# power.net
KiCad netlist of a schematic drawn in Altium Designer
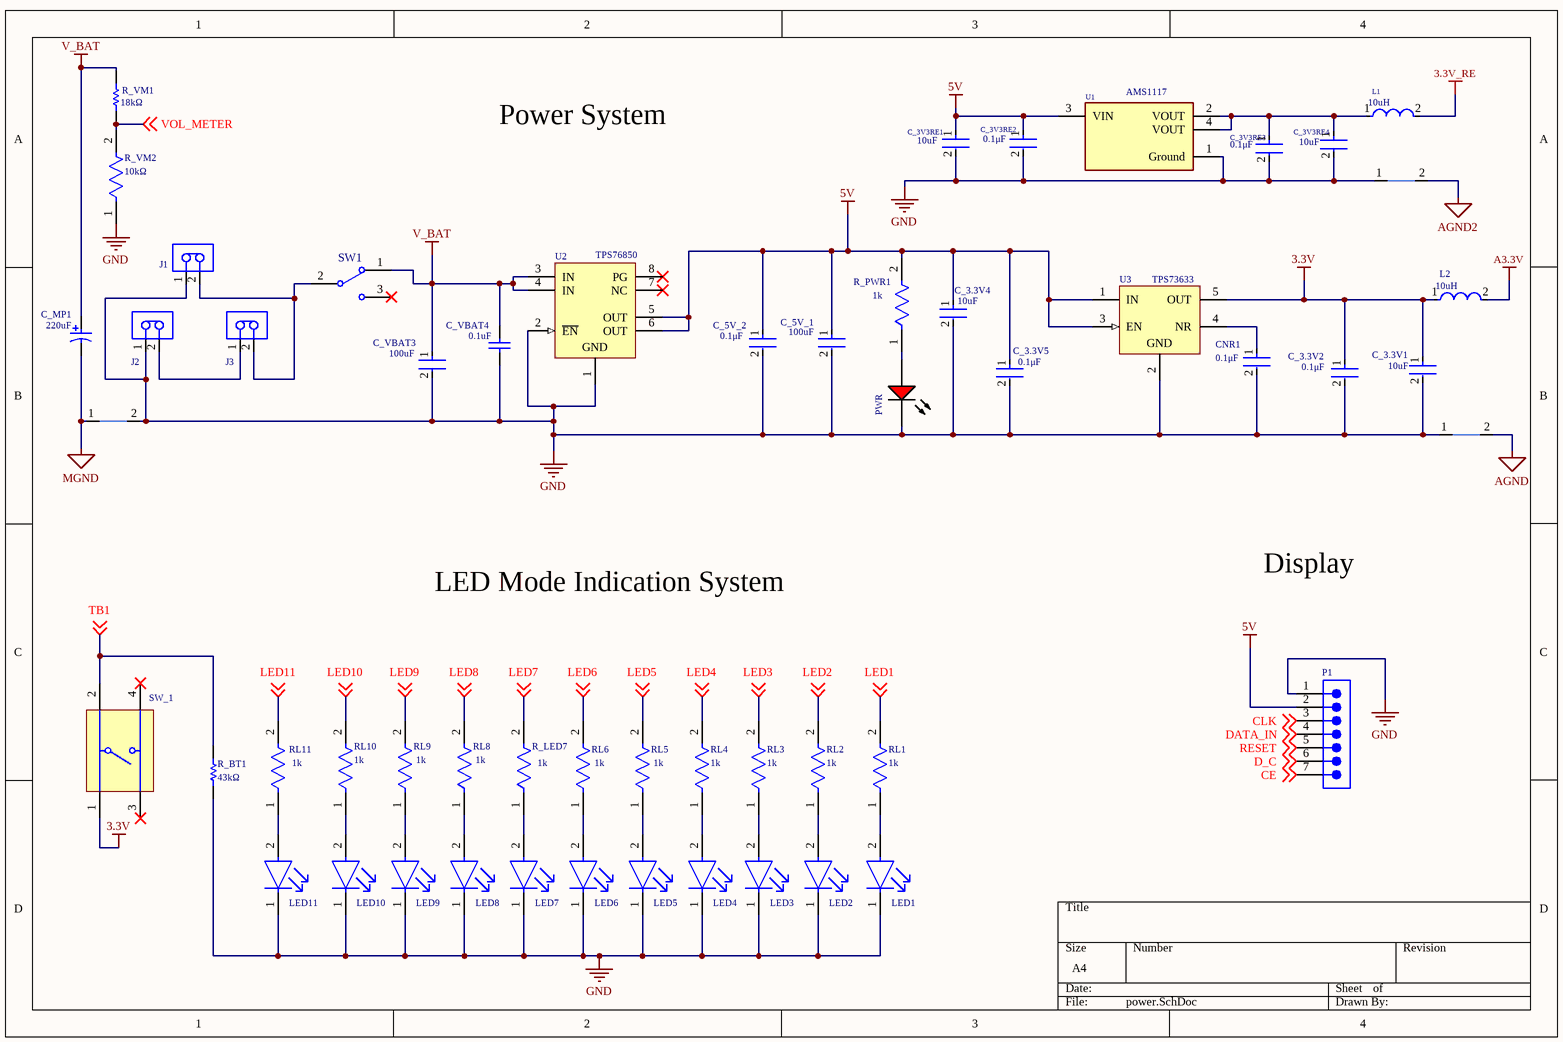
[diagram p0: power.SchDoc]

(export (version "E")
  (design (tool "Eeschema 10.0.6"))
  (components
    (comp (ref "CNR1")
      (value "0.1μF")
      (footprint "FP-C0805C-DN-MFG")
      (description "CAP CER 0.1UF 10V 5% X7R 0805")
      (fields (field (name "MANUFACTURER") "KEMET") (field (name "TOLERANCE") "0.05"))
      (libsource (lib "Altium Content Vault") (part "b4654b650e69147ec39a6b967a45e02"))
    )
    (comp (ref "C_3.3V1")
      (value "10uF")
      (footprint "FP-C0805C-DG-MFG")
      (description "CAP CER 10UF 10V X5R 0805")
      (fields (field (name "TOLERANCE") "10%") (field (name "MANUFACTURER PART NUMBER") "C0805C106K8PACTU"))
      (libsource (lib "Altium Content Vault") (part "11868f565c42a9108669ba33697ecf6"))
    )
    (comp (ref "C_3.3V2")
      (value "0.1μF")
      (footprint "FP-C0805C-DN-MFG")
      (description "CAP CER 0.1UF 10V 5% X7R 0805")
      (fields (field (name "MANUFACTURER") "KEMET") (field (name "TOLERANCE") "0.05"))
      (libsource (lib "Altium Content Vault") (part "b4654b650e69147ec39a6b967a45e02"))
    )
    (comp (ref "C_3.3V4")
      (value "10uF")
      (footprint "FP-C0805C-DG-MFG")
      (description "CAP CER 10UF 10V X5R 0805")
      (fields (field (name "TOLERANCE") "10%") (field (name "MANUFACTURER PART NUMBER") "C0805C106K8PACTU"))
      (libsource (lib "Altium Content Vault") (part "11868f565c42a9108669ba33697ecf6"))
    )
    (comp (ref "C_3.3V5")
      (value "0.1μF")
      (footprint "FP-C0805C-DN-MFG")
      (description "CAP CER 0.1UF 10V 5% X7R 0805")
      (fields (field (name "MANUFACTURER") "KEMET") (field (name "TOLERANCE") "0.05"))
      (libsource (lib "Altium Content Vault") (part "b4654b650e69147ec39a6b967a45e02"))
    )
    (comp (ref "C_3V3RE1")
      (value "10uF")
      (footprint "FP-C0805C-DG-MFG")
      (description "CAP CER 10UF 10V X5R 0805")
      (fields (field (name "TOLERANCE") "10%") (field (name "MANUFACTURER PART NUMBER") "C0805C106K8PACTU"))
      (libsource (lib "Altium Content Vault") (part "11868f565c42a9108669ba33697ecf6"))
    )
    (comp (ref "C_3V3RE2")
      (value "0.1μF")
      (footprint "FP-C0805C-DN-MFG")
      (description "CAP CER 0.1UF 10V 5% X7R 0805")
      (fields (field (name "MANUFACTURER") "KEMET") (field (name "TOLERANCE") "0.05"))
      (libsource (lib "Altium Content Vault") (part "b4654b650e69147ec39a6b967a45e02"))
    )
    (comp (ref "C_3V3RE3")
      (value "0.1μF")
      (footprint "FP-C0805C-DN-MFG")
      (description "CAP CER 0.1UF 10V 5% X7R 0805")
      (fields (field (name "MANUFACTURER") "KEMET") (field (name "TOLERANCE") "0.05"))
      (libsource (lib "Altium Content Vault") (part "b4654b650e69147ec39a6b967a45e02"))
    )
    (comp (ref "C_3V3RE4")
      (value "10uF")
      (footprint "FP-C0805C-DG-MFG")
      (description "CAP CER 10UF 10V X5R 0805")
      (fields (field (name "TOLERANCE") "10%") (field (name "MANUFACTURER PART NUMBER") "C0805C106K8PACTU"))
      (libsource (lib "Altium Content Vault") (part "11868f565c42a9108669ba33697ecf6"))
    )
    (comp (ref "C_5V_1")
      (value "100uF")
      (footprint "FP-C1206C-EH-MFG")
      (description "CAP CER 100UF 6.3V X5R 1206")
      (fields (field (name "TOLERANCE") "2%") (field (name "VOLTAGE") "6.3V"))
      (libsource (lib "Altium Content Vault") (part "02cd4be3c70576c341d710602a673aa"))
    )
    (comp (ref "C_5V_2")
      (value "0.1μF")
      (footprint "FP-C0805C-DN-MFG")
      (description "CAP CER 0.1UF 10V 5% X7R 0805")
      (fields (field (name "MANUFACTURER") "KEMET") (field (name "TOLERANCE") "0.05"))
      (libsource (lib "Altium Content Vault") (part "b4654b650e69147ec39a6b967a45e02"))
    )
    (comp (ref "C_MP1")
      (value "220uF")
      (footprint "NIC-CAPA2-6.3X7.7_V")
      (fields (field (name "PARTNUMBER") "UUD1A221MCL1GS") (field (name "MANUFACTURER") "Nichicon"))
      (libsource (lib "Altium Content Vault") (part "NIC-CAP-P-2"))
    )
    (comp (ref "C_VBAT3")
      (value "100uF")
      (footprint "FP-C1206C-EH-MFG")
      (description "CAP CER 100UF 6.3V X5R 1206")
      (fields (field (name "TOLERANCE") "2%") (field (name "VOLTAGE") "6.3V"))
      (libsource (lib "Altium Content Vault") (part "02cd4be3c70576c341d710602a673aa"))
    )
    (comp (ref "C_VBAT4")
      (value "0.1uF")
      (footprint "CAPC2013X145X50LL20T25")
      (fields (field (name "MANUFACTURER") "Kemet") (field (name "PART NUMBER") "C0805C105K4PACTU"))
      (libsource (lib "Altium Content Vault") (part "CAP"))
    )
    (comp (ref "J1")
      (value "B2B-PH-K-S(LF)(SN)")
      (footprint "JST-B2B-PH-K-S_V")
      (fields (field (name "MANUFACTURER") "JST"))
      (libsource (lib "Altium Content Vault") (part "CN-2P-F-QF2"))
    )
    (comp (ref "J2")
      (value "B2B-PH-K-S(LF)(SN)")
      (footprint "JST-B2B-PH-K-S_V")
      (fields (field (name "MANUFACTURER") "JST"))
      (libsource (lib "Altium Content Vault") (part "CN-2P-F-QF2"))
    )
    (comp (ref "J3")
      (value "B2B-PH-K-S(LF)(SN)")
      (footprint "JST-B2B-PH-K-S_V")
      (fields (field (name "MANUFACTURER") "JST"))
      (libsource (lib "Altium Content Vault") (part "CN-2P-F-QF2"))
    )
    (comp (ref "L1")
      (value "10uH")
      (footprint "FP-LB2012-1_25-0_2-MFG")
      (description "SMD Inductors 10uH ±10% 0.15A 0.468Ω 0805")
      (fields (field (name "TOLERANCE") "10%") (field (name "Comment") "LBR2012T100K"))
      (libsource (lib "Altium Content Vault") (part "725321dda6339637d4d059423bc1c3c"))
    )
    (comp (ref "L2")
      (value "10uH")
      (footprint "FP-LB2012-1_25-0_2-MFG")
      (description "SMD Inductors 10uH ±10% 0.15A 0.468Ω 0805")
      (fields (field (name "TOLERANCE") "10%") (field (name "Comment") "LBR2012T100K"))
      (libsource (lib "Altium Content Vault") (part "725321dda6339637d4d059423bc1c3c"))
    )
    (comp (ref "LED1")
      (value "SML-D12M1WT86")
      (footprint "FP-SML-D12-MFG")
      (description "LED YLW/GREEN DIFFUSED 1608 SMD")
      (fields
        (field (name "MANUFACTURER") "Rohm")
        (field (name "OCTOPART") "https://octopart.com/sml-d12m1wt86-rohm-70837112")
      )
      (libsource (lib "Altium Content Vault") (part "8706943c75ba83719d021d2fdc84c58"))
    )
    (comp (ref "LED2")
      (value "SML-D12M1WT86")
      (footprint "FP-SML-D12-MFG")
      (description "LED YLW/GREEN DIFFUSED 1608 SMD")
      (fields
        (field (name "MANUFACTURER") "Rohm")
        (field (name "OCTOPART") "https://octopart.com/sml-d12m1wt86-rohm-70837112")
      )
      (libsource (lib "Altium Content Vault") (part "8706943c75ba83719d021d2fdc84c58"))
    )
    (comp (ref "LED3")
      (value "SML-D12M1WT86")
      (footprint "FP-SML-D12-MFG")
      (description "LED YLW/GREEN DIFFUSED 1608 SMD")
      (fields
        (field (name "MANUFACTURER") "Rohm")
        (field (name "OCTOPART") "https://octopart.com/sml-d12m1wt86-rohm-70837112")
      )
      (libsource (lib "Altium Content Vault") (part "8706943c75ba83719d021d2fdc84c58"))
    )
    (comp (ref "LED4")
      (value "SML-D12M1WT86")
      (footprint "FP-SML-D12-MFG")
      (description "LED YLW/GREEN DIFFUSED 1608 SMD")
      (fields
        (field (name "MANUFACTURER") "Rohm")
        (field (name "OCTOPART") "https://octopart.com/sml-d12m1wt86-rohm-70837112")
      )
      (libsource (lib "Altium Content Vault") (part "8706943c75ba83719d021d2fdc84c58"))
    )
    (comp (ref "LED5")
      (value "SML-D12M1WT86")
      (footprint "FP-SML-D12-MFG")
      (description "LED YLW/GREEN DIFFUSED 1608 SMD")
      (fields
        (field (name "MANUFACTURER") "Rohm")
        (field (name "OCTOPART") "https://octopart.com/sml-d12m1wt86-rohm-70837112")
      )
      (libsource (lib "Altium Content Vault") (part "8706943c75ba83719d021d2fdc84c58"))
    )
    (comp (ref "LED6")
      (value "SML-D12M1WT86")
      (footprint "FP-SML-D12-MFG")
      (description "LED YLW/GREEN DIFFUSED 1608 SMD")
      (fields
        (field (name "MANUFACTURER") "Rohm")
        (field (name "OCTOPART") "https://octopart.com/sml-d12m1wt86-rohm-70837112")
      )
      (libsource (lib "Altium Content Vault") (part "8706943c75ba83719d021d2fdc84c58"))
    )
    (comp (ref "LED7")
      (value "SML-D12M1WT86")
      (footprint "FP-SML-D12-MFG")
      (description "LED YLW/GREEN DIFFUSED 1608 SMD")
      (fields
        (field (name "MANUFACTURER") "Rohm")
        (field (name "OCTOPART") "https://octopart.com/sml-d12m1wt86-rohm-70837112")
      )
      (libsource (lib "Altium Content Vault") (part "8706943c75ba83719d021d2fdc84c58"))
    )
    (comp (ref "LED8")
      (value "SML-D12M1WT86")
      (footprint "FP-SML-D12-MFG")
      (description "LED YLW/GREEN DIFFUSED 1608 SMD")
      (fields
        (field (name "MANUFACTURER") "Rohm")
        (field (name "OCTOPART") "https://octopart.com/sml-d12m1wt86-rohm-70837112")
      )
      (libsource (lib "Altium Content Vault") (part "8706943c75ba83719d021d2fdc84c58"))
    )
    (comp (ref "LED9")
      (value "SML-D12M1WT86")
      (footprint "FP-SML-D12-MFG")
      (description "LED YLW/GREEN DIFFUSED 1608 SMD")
      (fields
        (field (name "MANUFACTURER") "Rohm")
        (field (name "OCTOPART") "https://octopart.com/sml-d12m1wt86-rohm-70837112")
      )
      (libsource (lib "Altium Content Vault") (part "8706943c75ba83719d021d2fdc84c58"))
    )
    (comp (ref "LED10")
      (value "SML-D12M1WT86")
      (footprint "FP-SML-D12-MFG")
      (description "LED YLW/GREEN DIFFUSED 1608 SMD")
      (fields
        (field (name "MANUFACTURER") "Rohm")
        (field (name "OCTOPART") "https://octopart.com/sml-d12m1wt86-rohm-70837112")
      )
      (libsource (lib "Altium Content Vault") (part "8706943c75ba83719d021d2fdc84c58"))
    )
    (comp (ref "LED11")
      (value "SML-D12M1WT86")
      (footprint "FP-SML-D12-MFG")
      (description "LED YLW/GREEN DIFFUSED 1608 SMD")
      (fields
        (field (name "MANUFACTURER") "Rohm")
        (field (name "OCTOPART") "https://octopart.com/sml-d12m1wt86-rohm-70837112")
      )
      (libsource (lib "Altium Content Vault") (part "8706943c75ba83719d021d2fdc84c58"))
    )
    (comp (ref "NT1")
      (value "NT")
      (footprint "NETTIE_SMD")
      (description "Net Tie")
      (libsource (lib "NetTie") (part "NetTie_SMD"))
    )
    (comp (ref "NT2")
      (value "NT")
      (footprint "NETTIE_SMD")
      (description "Net Tie")
      (libsource (lib "NetTie") (part "NetTie_SMD"))
    )
    (comp (ref "NT3")
      (value "NT")
      (footprint "NETTIE_SMD")
      (description "Net Tie")
      (libsource (lib "NetTie") (part "NetTie_SMD"))
    )
    (comp (ref "P1")
      (value "61300711121")
      (footprint "61300711121")
      (libsource (lib "Altium Content Vault") (part "Header_Male_1R_07P"))
    )
    (comp (ref "PWR")
      (value "TLMS1100-GS08")
      (footprint "VISH-TLMX1100_V")
      (description "LED, RED, 2.1 V, -40 to 100 degC, 2-Pin SMD (0603), RoHS, Tape and Reel")
      (fields (field (name "TOLERANCE") "5%"))
      (libsource (lib "Altium Content Vault") (part "LED-RED-AK-2"))
    )
    (comp (ref "RL1")
      (value "1k")
      (footprint "FP-RC0603-0_55-IPC_C")
      (description "RES 1K OHM 1% 1/10W 0603")
      (fields (field (name "TOLERANCE") "1%") (field (name "Comment") "RC0603FR-071KL"))
      (libsource (lib "Altium Content Vault") (part "1029c3af85768c4190bb7ad29bc67b5"))
    )
    (comp (ref "RL2")
      (value "1k")
      (footprint "FP-RC0603-0_55-IPC_C")
      (description "RES 1K OHM 1% 1/10W 0603")
      (fields (field (name "TOLERANCE") "1%") (field (name "Comment") "RC0603FR-071KL"))
      (libsource (lib "Altium Content Vault") (part "1029c3af85768c4190bb7ad29bc67b5"))
    )
    (comp (ref "RL3")
      (value "1k")
      (footprint "FP-RC0603-0_55-IPC_C")
      (description "RES 1K OHM 1% 1/10W 0603")
      (fields (field (name "TOLERANCE") "1%") (field (name "Comment") "RC0603FR-071KL"))
      (libsource (lib "Altium Content Vault") (part "1029c3af85768c4190bb7ad29bc67b5"))
    )
    (comp (ref "RL4")
      (value "1k")
      (footprint "FP-RC0603-0_55-IPC_C")
      (description "RES 1K OHM 1% 1/10W 0603")
      (fields (field (name "TOLERANCE") "1%") (field (name "Comment") "RC0603FR-071KL"))
      (libsource (lib "Altium Content Vault") (part "1029c3af85768c4190bb7ad29bc67b5"))
    )
    (comp (ref "RL5")
      (value "1k")
      (footprint "FP-RC0603-0_55-IPC_C")
      (description "RES 1K OHM 1% 1/10W 0603")
      (fields (field (name "TOLERANCE") "1%") (field (name "Comment") "RC0603FR-071KL"))
      (libsource (lib "Altium Content Vault") (part "1029c3af85768c4190bb7ad29bc67b5"))
    )
    (comp (ref "RL6")
      (value "1k")
      (footprint "FP-RC0603-0_55-IPC_C")
      (description "RES 1K OHM 1% 1/10W 0603")
      (fields (field (name "TOLERANCE") "1%") (field (name "Comment") "RC0603FR-071KL"))
      (libsource (lib "Altium Content Vault") (part "1029c3af85768c4190bb7ad29bc67b5"))
    )
    (comp (ref "RL8")
      (value "1k")
      (footprint "FP-RC0603-0_55-IPC_C")
      (description "RES 1K OHM 1% 1/10W 0603")
      (fields (field (name "TOLERANCE") "1%") (field (name "Comment") "RC0603FR-071KL"))
      (libsource (lib "Altium Content Vault") (part "1029c3af85768c4190bb7ad29bc67b5"))
    )
    (comp (ref "RL9")
      (value "1k")
      (footprint "FP-RC0603-0_55-IPC_C")
      (description "RES 1K OHM 1% 1/10W 0603")
      (fields (field (name "TOLERANCE") "1%") (field (name "Comment") "RC0603FR-071KL"))
      (libsource (lib "Altium Content Vault") (part "1029c3af85768c4190bb7ad29bc67b5"))
    )
    (comp (ref "RL10")
      (value "1k")
      (footprint "FP-RC0603-0_55-IPC_C")
      (description "RES 1K OHM 1% 1/10W 0603")
      (fields (field (name "TOLERANCE") "1%") (field (name "Comment") "RC0603FR-071KL"))
      (libsource (lib "Altium Content Vault") (part "1029c3af85768c4190bb7ad29bc67b5"))
    )
    (comp (ref "RL11")
      (value "1k")
      (footprint "FP-RC0603-0_55-IPC_C")
      (description "RES 1K OHM 1% 1/10W 0603")
      (fields (field (name "TOLERANCE") "1%") (field (name "Comment") "RC0603FR-071KL"))
      (libsource (lib "Altium Content Vault") (part "1029c3af85768c4190bb7ad29bc67b5"))
    )
    (comp (ref "R_BT1")
      (value "43kΩ")
      (footprint "RESC1608X55X30NL20T20")
      (fields (field (name "PART NUMBER") "ERA3AEB433V") (field (name "MANUFACTURER") "Panasonic"))
      (libsource (lib "Altium Content Vault") (part "RES"))
    )
    (comp (ref "R_LED7")
      (value "1k")
      (footprint "FP-RC0603-0_55-IPC_C")
      (description "RES 1K OHM 1% 1/10W 0603")
      (fields (field (name "TOLERANCE") "1%") (field (name "Comment") "RC0603FR-071KL"))
      (libsource (lib "Altium Content Vault") (part "1029c3af85768c4190bb7ad29bc67b5"))
    )
    (comp (ref "R_PWR1")
      (value "1k")
      (footprint "FP-RC0603-0_55-IPC_C")
      (description "RES 1K OHM 1% 1/10W 0603")
      (fields (field (name "TOLERANCE") "1%") (field (name "Comment") "RC0603FR-071KL"))
      (libsource (lib "Altium Content Vault") (part "1029c3af85768c4190bb7ad29bc67b5"))
    )
    (comp (ref "R_VM1")
      (value "18kΩ")
      (footprint "RESC1608X55X30ML15T15")
      (fields (field (name "PART NUMBER") "ERJ-3EKF2002V") (field (name "MANUFACTURER") "Panasonic"))
      (libsource (lib "Altium Content Vault") (part "RES"))
    )
    (comp (ref "R_VM2")
      (value "10kΩ")
      (footprint "FP-ERA3A-IPC_C")
      (description "RES SMD 10K OHM 0.1% 1/10W 0603")
      (fields (field (name "TOLERANCE") "0.1%") (field (name "Comment") "ERA-3AEB103V"))
      (libsource (lib "Altium Content Vault") (part "4e5f8b3dd332802e91518312df5df73"))
    )
    (comp (ref "SW1")
      (value "EG1218")
      (footprint "ESWI-EG1218_V")
      (description "Slide Switch, 500 V, -20 to 70 degC, 3-Pin THD, RoHS")
      (libsource (lib "Altium Content Vault") (part "SW-SPDT-3_B"))
    )
    (comp (ref "SW_1")
      (value "1825910-6")
      (footprint "TECO-1825910-6_V")
      (description "Tact Switch, SPST-NO, 0.05 A, -35 to 85 degC, 4-Pin THD, RoHS, Bulk")
      (fields (field (name "MANUFACTURER") "TE Connectivity"))
      (libsource (lib "Altium Content Vault") (part "SW-SPST-4_A"))
    )
    (comp (ref "U1")
      (value "AMS1117")
      (footprint "FP-AMS1117-IPC_C")
      (description "LDO Voltage Regulators 1A, 3.3V")
      (fields
        (field (name "MANUFACTURER PART NUMBER") "AMS1117-3.3")
        (field (name "OCTOPART") "https://octopart.com/ams1117-3.3-advanced+monolithic+systems-25899300")
      )
      (libsource (lib "Altium Content Vault") (part "8bdbb5f8e77002000e30dd2845d0354"))
    )
    (comp (ref "U2")
      (value "TPS76850")
      (footprint "D0008A_N")
      (fields (field (name "PARTNUMBER") "TPS76850QDR") (field (name "MANUFACTURER") "Texas Instruments"))
      (libsource (lib "Altium Content Vault") (part "TI-TPS7XXXXD8_A"))
    )
    (comp (ref "U3")
      (value "TPS73633")
      (footprint "DBV0005A_L")
      (fields (field (name "PARTNUMBER") "TPS73633DBVR") (field (name "MANUFACTURER") "Texas Instruments"))
      (libsource (lib "Altium Content Vault") (part "TI-TPS79NXX-YYSOT5"))
    )
  )
  (nets
    (net (code "1") (name "3.3V") (class "Default")
      (node (ref "C_3.3V1") (pin "1") (pinfunction "1_1") (pintype "passive"))
      (node (ref "C_3.3V2") (pin "1") (pinfunction "1_1") (pintype "passive"))
      (node (ref "L2") (pin "1") (pinfunction "1_1") (pintype "passive"))
      (node (ref "SW_1") (pin "1") (pinfunction "1_1") (pintype "passive"))
      (node (ref "U3") (pin "5") (pinfunction "OUT_5") (pintype "power_in"))
    )
    (net (code "2") (name "3.3V_RE") (class "Default")
      (node (ref "L1") (pin "2") (pinfunction "2_2") (pintype "passive"))
    )
    (net (code "3") (name "5V") (class "Default")
      (node (ref "C_3.3V4") (pin "1") (pinfunction "1_1") (pintype "passive"))
      (node (ref "C_3.3V5") (pin "1") (pinfunction "1_1") (pintype "passive"))
      (node (ref "C_3V3RE1") (pin "1") (pinfunction "1_1") (pintype "passive"))
      (node (ref "C_3V3RE2") (pin "1") (pinfunction "1_1") (pintype "passive"))
      (node (ref "C_5V_1") (pin "1") (pinfunction "1_1") (pintype "passive"))
      (node (ref "C_5V_2") (pin "1") (pinfunction "1_1") (pintype "passive"))
      (node (ref "P1") (pin "2") (pinfunction "2_2") (pintype "passive"))
      (node (ref "R_PWR1") (pin "2") (pinfunction "2_2") (pintype "passive"))
      (node (ref "U1") (pin "3") (pinfunction "VIN_3") (pintype "power_in"))
      (node (ref "U2") (pin "5") (pinfunction "OUT_5") (pintype "power_in"))
      (node (ref "U2") (pin "6") (pinfunction "OUT_6") (pintype "power_in"))
      (node (ref "U3") (pin "1") (pinfunction "IN_1") (pintype "power_in"))
      (node (ref "U3") (pin "3") (pinfunction "EN_3") (pintype "input"))
    )
    (net (code "4") (name "A3.3V") (class "Default")
      (node (ref "L2") (pin "2") (pinfunction "2_2") (pintype "passive"))
    )
    (net (code "5") (name "AGND") (class "Default")
      (node (ref "NT2") (pin "2") (pinfunction "2_2") (pintype "passive"))
    )
    (net (code "6") (name "AGND2") (class "Default")
      (node (ref "NT3") (pin "2") (pinfunction "2_2") (pintype "passive"))
    )
    (net (code "7") (name "CE") (class "Default")
      (node (ref "P1") (pin "7") (pinfunction "7_7") (pintype "passive"))
    )
    (net (code "8") (name "CLK") (class "Default")
      (node (ref "P1") (pin "3") (pinfunction "3_3") (pintype "passive"))
    )
    (net (code "9") (name "DATA_IN") (class "Default")
      (node (ref "P1") (pin "4") (pinfunction "4_4") (pintype "passive"))
    )
    (net (code "10") (name "D_C") (class "Default")
      (node (ref "P1") (pin "6") (pinfunction "6_6") (pintype "passive"))
    )
    (net (code "11") (name "GND") (class "Default")
      (node (ref "CNR1") (pin "2") (pinfunction "2_2") (pintype "passive"))
      (node (ref "C_3.3V1") (pin "2") (pinfunction "2_2") (pintype "passive"))
      (node (ref "C_3.3V2") (pin "2") (pinfunction "2_2") (pintype "passive"))
      (node (ref "C_3.3V4") (pin "2") (pinfunction "2_2") (pintype "passive"))
      (node (ref "C_3.3V5") (pin "2") (pinfunction "2_2") (pintype "passive"))
      (node (ref "C_3V3RE1") (pin "2") (pinfunction "2_2") (pintype "passive"))
      (node (ref "C_3V3RE2") (pin "2") (pinfunction "2_2") (pintype "passive"))
      (node (ref "C_3V3RE3") (pin "2") (pinfunction "2_2") (pintype "passive"))
      (node (ref "C_3V3RE4") (pin "2") (pinfunction "2_2") (pintype "passive"))
      (node (ref "C_5V_1") (pin "2") (pinfunction "2_2") (pintype "passive"))
      (node (ref "C_5V_2") (pin "2") (pinfunction "2_2") (pintype "passive"))
      (node (ref "C_VBAT3") (pin "2") (pinfunction "2_2") (pintype "passive"))
      (node (ref "C_VBAT4") (pin "1") (pinfunction "1_1") (pintype "passive"))
      (node (ref "J1") (pin "1") (pinfunction "1_1") (pintype "passive"))
      (node (ref "J2") (pin "1") (pinfunction "1_1") (pintype "passive"))
      (node (ref "LED1") (pin "1") (pinfunction "C_1") (pintype "passive"))
      (node (ref "LED10") (pin "1") (pinfunction "C_1") (pintype "passive"))
      (node (ref "LED11") (pin "1") (pinfunction "C_1") (pintype "passive"))
      (node (ref "LED2") (pin "1") (pinfunction "C_1") (pintype "passive"))
      (node (ref "LED3") (pin "1") (pinfunction "C_1") (pintype "passive"))
      (node (ref "LED4") (pin "1") (pinfunction "C_1") (pintype "passive"))
      (node (ref "LED5") (pin "1") (pinfunction "C_1") (pintype "passive"))
      (node (ref "LED6") (pin "1") (pinfunction "C_1") (pintype "passive"))
      (node (ref "LED7") (pin "1") (pinfunction "C_1") (pintype "passive"))
      (node (ref "LED8") (pin "1") (pinfunction "C_1") (pintype "passive"))
      (node (ref "LED9") (pin "1") (pinfunction "C_1") (pintype "passive"))
      (node (ref "NT1") (pin "2") (pinfunction "2_2") (pintype "passive"))
      (node (ref "NT2") (pin "1") (pinfunction "1_1") (pintype "passive"))
      (node (ref "NT3") (pin "1") (pinfunction "1_1") (pintype "passive"))
      (node (ref "P1") (pin "1") (pinfunction "1_1") (pintype "passive"))
      (node (ref "PWR") (pin "2") (pinfunction "K_2") (pintype "passive"))
      (node (ref "R_BT1") (pin "1") (pinfunction "1_1") (pintype "passive"))
      (node (ref "R_VM2") (pin "1") (pinfunction "1_1") (pintype "passive"))
      (node (ref "U1") (pin "1") (pinfunction "Ground_1") (pintype "power_in"))
      (node (ref "U2") (pin "1") (pinfunction "GND_1") (pintype "power_in"))
      (node (ref "U2") (pin "2") (pinfunction "~{EN}_2") (pintype "input"))
      (node (ref "U3") (pin "2") (pinfunction "GND_2") (pintype "power_in"))
    )
    (net (code "12") (name "LED1") (class "Default")
      (node (ref "RL1") (pin "2") (pinfunction "2_2") (pintype "passive"))
    )
    (net (code "13") (name "LED2") (class "Default")
      (node (ref "RL2") (pin "2") (pinfunction "2_2") (pintype "passive"))
    )
    (net (code "14") (name "LED3") (class "Default")
      (node (ref "RL3") (pin "2") (pinfunction "2_2") (pintype "passive"))
    )
    (net (code "15") (name "LED4") (class "Default")
      (node (ref "RL4") (pin "2") (pinfunction "2_2") (pintype "passive"))
    )
    (net (code "16") (name "LED5") (class "Default")
      (node (ref "RL5") (pin "2") (pinfunction "2_2") (pintype "passive"))
    )
    (net (code "17") (name "LED6") (class "Default")
      (node (ref "RL6") (pin "2") (pinfunction "2_2") (pintype "passive"))
    )
    (net (code "18") (name "LED7") (class "Default")
      (node (ref "R_LED7") (pin "2") (pinfunction "2_2") (pintype "passive"))
    )
    (net (code "19") (name "LED8") (class "Default")
      (node (ref "RL8") (pin "2") (pinfunction "2_2") (pintype "passive"))
    )
    (net (code "20") (name "LED9") (class "Default")
      (node (ref "RL9") (pin "2") (pinfunction "2_2") (pintype "passive"))
    )
    (net (code "21") (name "LED10") (class "Default")
      (node (ref "RL10") (pin "2") (pinfunction "2_2") (pintype "passive"))
    )
    (net (code "22") (name "LED11") (class "Default")
      (node (ref "RL11") (pin "2") (pinfunction "2_2") (pintype "passive"))
    )
    (net (code "23") (name "MGND") (class "Default")
      (node (ref "C_MP1") (pin "2") (pinfunction "2_2") (pintype "passive"))
      (node (ref "NT1") (pin "1") (pinfunction "1_1") (pintype "passive"))
    )
    (net (code "24") (name "Net-(C_3V3RE3-Pad1)") (class "Default")
      (node (ref "C_3V3RE3") (pin "1") (pinfunction "1_1") (pintype "passive"))
      (node (ref "C_3V3RE4") (pin "1") (pinfunction "1_1") (pintype "passive"))
      (node (ref "L1") (pin "1") (pinfunction "1_1") (pintype "passive"))
      (node (ref "U1") (pin "2") (pinfunction "VOUT_2") (pintype "passive"))
      (node (ref "U1") (pin "4") (pinfunction "VOUT_4") (pintype "passive"))
    )
    (net (code "25") (name "Net-(J2-Pad2)") (class "Default")
      (node (ref "J2") (pin "2") (pinfunction "2_2") (pintype "passive"))
      (node (ref "J3") (pin "1") (pinfunction "1_1") (pintype "passive"))
    )
    (net (code "26") (name "Net-(LED1-A)") (class "Default")
      (node (ref "LED1") (pin "2") (pinfunction "A_2") (pintype "passive"))
      (node (ref "RL1") (pin "1") (pinfunction "1_1") (pintype "passive"))
    )
    (net (code "27") (name "Net-(LED2-A)") (class "Default")
      (node (ref "LED2") (pin "2") (pinfunction "A_2") (pintype "passive"))
      (node (ref "RL2") (pin "1") (pinfunction "1_1") (pintype "passive"))
    )
    (net (code "28") (name "Net-(LED3-A)") (class "Default")
      (node (ref "LED3") (pin "2") (pinfunction "A_2") (pintype "passive"))
      (node (ref "RL3") (pin "1") (pinfunction "1_1") (pintype "passive"))
    )
    (net (code "29") (name "Net-(LED4-A)") (class "Default")
      (node (ref "LED4") (pin "2") (pinfunction "A_2") (pintype "passive"))
      (node (ref "RL4") (pin "1") (pinfunction "1_1") (pintype "passive"))
    )
    (net (code "30") (name "Net-(LED5-A)") (class "Default")
      (node (ref "LED5") (pin "2") (pinfunction "A_2") (pintype "passive"))
      (node (ref "RL5") (pin "1") (pinfunction "1_1") (pintype "passive"))
    )
    (net (code "31") (name "Net-(LED6-A)") (class "Default")
      (node (ref "LED6") (pin "2") (pinfunction "A_2") (pintype "passive"))
      (node (ref "RL6") (pin "1") (pinfunction "1_1") (pintype "passive"))
    )
    (net (code "32") (name "Net-(LED7-A)") (class "Default")
      (node (ref "LED7") (pin "2") (pinfunction "A_2") (pintype "passive"))
      (node (ref "R_LED7") (pin "1") (pinfunction "1_1") (pintype "passive"))
    )
    (net (code "33") (name "Net-(LED8-A)") (class "Default")
      (node (ref "LED8") (pin "2") (pinfunction "A_2") (pintype "passive"))
      (node (ref "RL8") (pin "1") (pinfunction "1_1") (pintype "passive"))
    )
    (net (code "34") (name "Net-(LED9-A)") (class "Default")
      (node (ref "LED9") (pin "2") (pinfunction "A_2") (pintype "passive"))
      (node (ref "RL9") (pin "1") (pinfunction "1_1") (pintype "passive"))
    )
    (net (code "35") (name "Net-(LED10-A)") (class "Default")
      (node (ref "LED10") (pin "2") (pinfunction "A_2") (pintype "passive"))
      (node (ref "RL10") (pin "1") (pinfunction "1_1") (pintype "passive"))
    )
    (net (code "36") (name "Net-(LED11-A)") (class "Default")
      (node (ref "LED11") (pin "2") (pinfunction "A_2") (pintype "passive"))
      (node (ref "RL11") (pin "1") (pinfunction "1_1") (pintype "passive"))
    )
    (net (code "37") (name "Net-(PWR-A)") (class "Default")
      (node (ref "PWR") (pin "1") (pinfunction "A_1") (pintype "passive"))
      (node (ref "R_PWR1") (pin "1") (pinfunction "1_1") (pintype "passive"))
    )
    (net (code "38") (name "Net-(SW1-COM)") (class "Default")
      (node (ref "J1") (pin "2") (pinfunction "2_2") (pintype "passive"))
      (node (ref "J3") (pin "2") (pinfunction "2_2") (pintype "passive"))
      (node (ref "SW1") (pin "2") (pinfunction "COM_2") (pintype "passive"))
    )
    (net (code "39") (name "Net-(U3-NR)") (class "Default")
      (node (ref "CNR1") (pin "1") (pinfunction "1_1") (pintype "passive"))
      (node (ref "U3") (pin "4") (pinfunction "NR_4") (pintype "passive"))
    )
    (net (code "40") (name "RESET") (class "Default")
      (node (ref "P1") (pin "5") (pinfunction "5_5") (pintype "passive"))
    )
    (net (code "41") (name "TB1") (class "Default")
      (node (ref "R_BT1") (pin "2") (pinfunction "2_2") (pintype "passive"))
      (node (ref "SW_1") (pin "2") (pinfunction "2_2") (pintype "passive"))
    )
    (net (code "42") (name "VOL_METER") (class "Default")
      (node (ref "R_VM1") (pin "1") (pinfunction "1_1") (pintype "passive"))
      (node (ref "R_VM2") (pin "2") (pinfunction "2_2") (pintype "passive"))
    )
    (net (code "43") (name "V_BAT") (class "Default")
      (node (ref "C_MP1") (pin "1") (pinfunction "1_1") (pintype "passive"))
      (node (ref "C_VBAT3") (pin "1") (pinfunction "1_1") (pintype "passive"))
      (node (ref "C_VBAT4") (pin "2") (pinfunction "2_2") (pintype "passive"))
      (node (ref "R_VM1") (pin "2") (pinfunction "2_2") (pintype "passive"))
      (node (ref "SW1") (pin "1") (pinfunction "1_1") (pintype "passive"))
      (node (ref "U2") (pin "3") (pinfunction "IN_3") (pintype "power_in"))
      (node (ref "U2") (pin "4") (pinfunction "IN_4") (pintype "power_in"))
    )
    (net (code "44") (name "unconnected-(SW1-Pad3)") (class "Default")
      (node (ref "SW1") (pin "3") (pinfunction "3_3") (pintype "passive+no_connect"))
    )
    (net (code "45") (name "unconnected-(SW_1-Pad3)") (class "Default")
      (node (ref "SW_1") (pin "3") (pinfunction "3_3") (pintype "passive+no_connect"))
    )
    (net (code "46") (name "unconnected-(SW_1-Pad4)") (class "Default")
      (node (ref "SW_1") (pin "4") (pinfunction "4_4") (pintype "passive+no_connect"))
    )
    (net (code "47") (name "unconnected-(U2-NC-Pad7)") (class "Default")
      (node (ref "U2") (pin "7") (pinfunction "NC_7") (pintype "passive+no_connect"))
    )
    (net (code "48") (name "unconnected-(U2-PG-Pad8)") (class "Default")
      (node (ref "U2") (pin "8") (pinfunction "PG_8") (pintype "tri_state+no_connect"))
    )
  )
)
